# RF-learn-command-1relay-220V-capacitor.net
KiCad netlist of a schematic drawn in Altium Designer
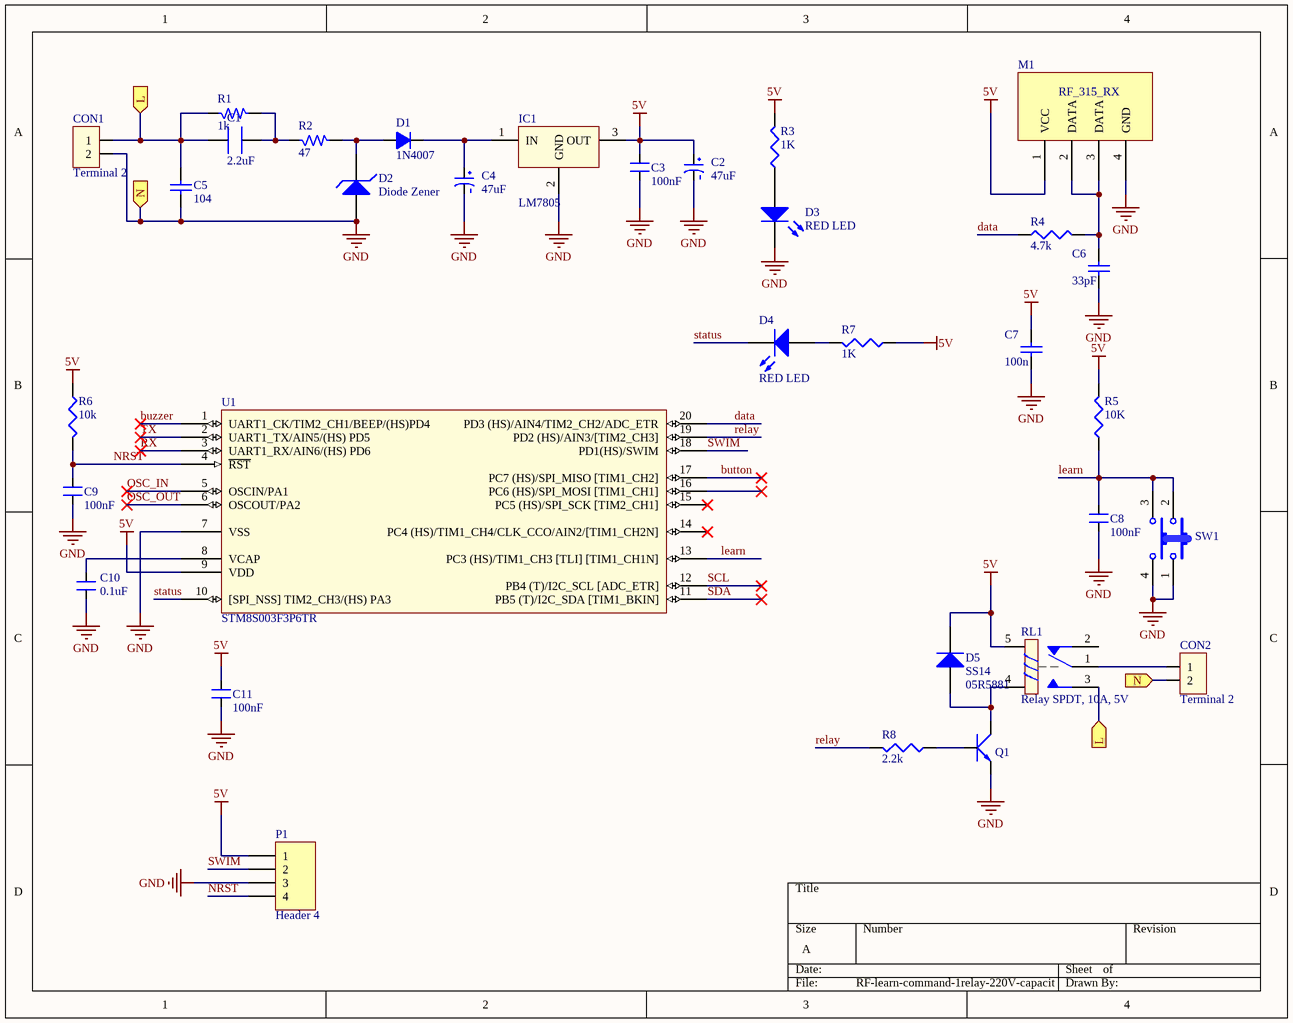
[diagram p0: RF-learn-command-1relay-220V-capacitor.SchDoc]

(export (version "E")
  (design (tool "Eeschema 10.0.6"))
  (components
    (comp (ref "C1")
      (value "2.2uF")
      (footprint "CAP 400V POLY")
      (description "DIP Electrolytic Capacitors")
      (fields (field (name "VOLTAGE") "400V") (field (name "TOLERANCE") "20%"))
      (libsource (lib "SS_Basic") (part "CAP Polyester"))
    )
    (comp (ref "C2")
      (value "47uF")
      (footprint "Capacitor 6.3")
      (description "DIP Electrolytic Capacitors")
      (fields (field (name "VOLTAGE") "35V") (field (name "TOLERANCE") "20%"))
      (libsource (lib "SS_Basic") (part "CAP DIP"))
    )
    (comp (ref "C3")
      (value "100nF")
      (footprint "ST:CM 0805")
      (description "SMD Ceramic  Capacitor")
      (fields (field (name "VOLTAGE") "50V") (field (name "TOLERANCE") "10%"))
      (libsource (lib "ST") (part "CM Ceramic"))
    )
    (comp (ref "C4")
      (value "47uF")
      (footprint "Capacitor 6.3")
      (description "DIP Electrolytic Capacitors")
      (fields (field (name "VOLTAGE") "35V") (field (name "TOLERANCE") "20%"))
      (libsource (lib "SS_Basic") (part "CAP DIP"))
    )
    (comp (ref "C5")
      (value "104")
      (footprint "C_Ceramic_KV")
      (description "Polar Capacitor")
      (fields (field (name "Comment") "Cap1") (field (name "PUBLISHER") "Altium Limited"))
      (libsource (lib "SS_Basic") (part "Cap1"))
    )
    (comp (ref "C6")
      (value "33pF")
      (footprint "ST:CM 0805")
      (description "Capacitor 100n 16V 0603")
      (fields (field (name "PUBLISHER") "Altium Limited"))
      (libsource (lib "Capacitor") (part "Cap Semi"))
    )
    (comp (ref "C7")
      (value "100n")
      (footprint "ST:CM 0805")
      (description "Capacitor 100n 16V 0603")
      (fields (field (name "PUBLISHER") "Altium Limited"))
      (libsource (lib "Capacitor") (part "Cap Semi"))
    )
    (comp (ref "C8")
      (value "100nF")
      (footprint "ST:CM 0805")
      (description "SMD Ceramic  Capacitor")
      (fields (field (name "VOLTAGE") "50V") (field (name "TOLERANCE") "10%"))
      (libsource (lib "ST") (part "CM Ceramic"))
    )
    (comp (ref "C9")
      (value "100nF")
      (footprint "ST:CM 0805")
      (description "SMD Ceramic  Capacitor")
      (fields (field (name "VOLTAGE") "50V") (field (name "TOLERANCE") "10%"))
      (libsource (lib "ST") (part "CM Ceramic"))
    )
    (comp (ref "C10")
      (value "0.1uF")
      (footprint "ST:CM 0805")
      (description "SMD Ceramic  Capacitor")
      (fields (field (name "VOLTAGE") "50V") (field (name "TOLERANCE") "10%"))
      (libsource (lib "ST") (part "CM Ceramic"))
    )
    (comp (ref "C11")
      (value "100nF")
      (footprint "ST:CM 0805")
      (description "SMD Ceramic  Capacitor")
      (fields (field (name "VOLTAGE") "50V") (field (name "TOLERANCE") "10%"))
      (libsource (lib "ST") (part "CM Ceramic"))
    )
    (comp (ref "CON1")
      (value "Terminal 2")
      (footprint "RF-learn-command-1relay-220V-capacitor:Terminal 2 5.08")
      (libsource (lib "SS_Con") (part "Terminal 2"))
    )
    (comp (ref "CON2")
      (value "Terminal 2")
      (footprint "RF-learn-command-1relay-220V-capacitor:Terminal 2 5.08")
      (libsource (lib "") (part "Terminal 2_1"))
    )
    (comp (ref "D1")
      (value "1N4007")
      (footprint "DO-214AC")
      (description "1N4007 Rectifier Diodes")
      (fields (field (name "MANUFACTURER") "SYC"))
      (libsource (lib "SS_Basic") (part "Diodes Rectifier"))
    )
    (comp (ref "D2")
      (value "Diode Zener")
      (footprint "SOD-123")
      (description "Zener Voltage Regulators")
      (fields (field (name "MANUFACTURER") "ON Semiconductor"))
      (libsource (lib "SS_Basic") (part "Diode Zener"))
    )
    (comp (ref "D3")
      (value "RED LED")
      (footprint "LED0805-R")
      (description "LED SUPR RED CLR 0805 RT ANG SMD")
      (fields
        (field (name "DIGI-KEY PART NUMBER") "160-1469-2-ND")
        (field (name "MANUFACTURER") "Lite-On Inc")
        (field (name "PUBLISHER") "Altium Limited")
      )
      (libsource (lib "Miscellaneous Devices") (part "LED2"))
    )
    (comp (ref "D4")
      (value "RED LED")
      (footprint "LED:LED3mm-Y")
      (description "LED SUPR RED CLR 0805 RT ANG SMD")
      (fields
        (field (name "DIGI-KEY PART NUMBER") "160-1469-2-ND")
        (field (name "MANUFACTURER") "Lite-On Inc")
        (field (name "PUBLISHER") "Altium Limited")
      )
      (libsource (lib "Miscellaneous Devices") (part "LED2"))
    )
    (comp (ref "D5")
      (value "SS14")
      (footprint "DO-214AC (SMA)")
      (description "DIODE GEN PURPOSE 1000V 1A SMA")
      (fields
        (field (name "DIGI-KEY PART NUMBER") "641-1018-1-ND")
        (field (name "MANUFACTURER PART NUMBER") "CGRA4007-G")
        (field (name "SUPPLIER PART NUMBER 1") "05R5881")
        (field (name "PUBLISHER") "Altium Limited")
      )
      (libsource (lib "Miscellaneous Devices") (part "Diode"))
    )
    (comp (ref "IC1")
      (value "LM7805")
      (footprint "ST:TO-252-3-L1")
      (description "On ap +, from + 5 to + 24VDC")
      (libsource (lib "syhaunguyen") (part "LM78xx"))
    )
    (comp (ref "M1")
      (value "RF_315_RX")
      (footprint "module-lib:Module-RF-RX")
      (libsource (lib "module-lib") (part "ModuleRF-RX"))
    )
    (comp (ref "P1")
      (value "Header 4")
      (footprint "SS_Con:HDR1X4")
      (description "Header, 4-Pin")
      (fields (field (name "PUBLISHER") "Altium Limited"))
      (libsource (lib "SS_Con") (part "Header 4"))
    )
    (comp (ref "Q1")
      (value "C1815")
      (footprint "2SC1815")
      (description "NPN SMD Transistor")
      (fields (field (name "MANUFACTURER") "Toshiba"))
      (libsource (lib "ST") (part "C1815"))
    )
    (comp (ref "R1")
      (value "1k")
      (footprint "R 1/4W")
      (description "Resistor 1/4W DIP")
      (libsource (lib "SS_Basic") (part "R1/4W"))
    )
    (comp (ref "R2")
      (value "47")
      (footprint "SS_Basic:R 1WD")
      (description "Resistor 1/2W DIP")
      (fields (field (name "MANUFACTURER") "UniOhm"))
      (libsource (lib "SS_Basic") (part "R1/2W"))
    )
    (comp (ref "R3")
      (value "1K")
      (footprint "R0805")
      (description "Resistor 10k 0603")
      (fields (field (name "PUBLISHER") "Altium Limited"))
      (libsource (lib "Miscellaneous Devices") (part "Res3"))
    )
    (comp (ref "R4")
      (value "4.7k")
      (footprint "R0805")
      (description "Resistor")
      (fields
        (field (name "MANUFACTURER") "Vishay / Draloric")
        (field (name "MANUFACTURER PART NUMBER") "RCV0805301KFKEA")
        (field (name "PUBLISHER") "Altium Limited")
      )
      (libsource (lib "altium-import") (part "root_0_Res3_"))
    )
    (comp (ref "R5")
      (value "10K")
      (footprint "R0805")
      (description "Resistor 10k 0603")
      (fields (field (name "PUBLISHER") "Altium Limited"))
      (libsource (lib "Miscellaneous Devices") (part "Res3"))
    )
    (comp (ref "R6")
      (value "10k")
      (footprint "R0805")
      (description "Resistor")
      (fields
        (field (name "MANUFACTURER") "Vishay / Draloric")
        (field (name "MANUFACTURER PART NUMBER") "RCV0805301KFKEA")
        (field (name "PUBLISHER") "Altium Limited")
      )
      (libsource (lib "altium-import") (part "root_3_Res3_"))
    )
    (comp (ref "R7")
      (value "1K")
      (footprint "R0805")
      (description "Resistor 10k 0603")
      (fields (field (name "PUBLISHER") "Altium Limited"))
      (libsource (lib "Miscellaneous Devices") (part "Res3"))
    )
    (comp (ref "R8")
      (value "2.2k")
      (footprint "R0805")
      (description "Resistor")
      (fields
        (field (name "MANUFACTURER") "Vishay / Draloric")
        (field (name "MANUFACTURER PART NUMBER") "RCV0805301KFKEA")
        (field (name "PUBLISHER") "Altium Limited")
      )
      (libsource (lib "altium-import") (part "root_2_Res3_"))
    )
    (comp (ref "RL1")
      (value "Relay SPDT, 10A, 5V")
      (footprint "RL_SPDT_10A")
      (description "Relay SPDT,10A - 12VDC 5 Pin")
      (libsource (lib "nhantt-relay-lib") (part "Relay 1"))
    )
    (comp (ref "SW1")
      (value "SW-4P-S")
      (footprint "SW4")
      (description "Switch Small 4 Pin")
      (fields (field (name "PUBLISHER") "Altium Limited"))
      (libsource (lib "Schematic") (part "SW-4PIN-SMALL"))
    )
    (comp (ref "U1")
      (value "STM8S003F3P6TR")
      (footprint "SSOP-20")
      (description "MCU")
      (fields (field (name "MANUFACTURER") "STMicroelectronics"))
      (libsource (lib "mcu-lib") (part "STM8S003F3"))
    )
  )
  (nets
    (net (code "1") (name "/L") (class "Default")
      (node (ref "C1") (pin "1") (pinfunction "1_1") (pintype "passive"))
      (node (ref "C5") (pin "2") (pinfunction "2_2") (pintype "passive"))
      (node (ref "CON1") (pin "1") (pinfunction "1_1") (pintype "passive"))
      (node (ref "R1") (pin "1") (pinfunction "1_1") (pintype "passive"))
      (node (ref "RL1") (pin "3") (pinfunction "3_3") (pintype "passive"))
    )
    (net (code "2") (name "/NRST") (class "Default")
      (node (ref "C9") (pin "2") (pinfunction "2_2") (pintype "passive"))
      (node (ref "P1") (pin "4") (pinfunction "4_4") (pintype "passive"))
      (node (ref "R6") (pin "2") (pinfunction "2_2") (pintype "passive"))
      (node (ref "U1") (pin "4") (pinfunction "~{RST}_4") (pintype "input"))
    )
    (net (code "3") (name "/OSC_IN") (class "Default")
      (node (ref "U1") (pin "5") (pinfunction "OSCIN/PA1_5") (pintype "bidirectional+no_connect"))
    )
    (net (code "4") (name "/OSC_OUT") (class "Default")
      (node (ref "U1") (pin "6") (pinfunction "OSCOUT/PA2_6") (pintype "bidirectional+no_connect"))
    )
    (net (code "5") (name "/RX") (class "Default")
      (node (ref "U1") (pin "3") (pinfunction "UART1_RX/AIN6/(HS)_PD6_3") (pintype "bidirectional+no_connect"))
    )
    (net (code "6") (name "/SCL") (class "Default")
      (node (ref "U1") (pin "12") (pinfunction "PB4_(T)/I2C_SCL_[ADC_ETR]_12") (pintype "bidirectional+no_connect"))
    )
    (net (code "7") (name "/SDA") (class "Default")
      (node (ref "U1") (pin "11") (pinfunction "PB5_(T)/I2C_SDA_[TIM1_BKIN]_11") (pintype "bidirectional+no_connect"))
    )
    (net (code "8") (name "/SWIM") (class "Default")
      (node (ref "P1") (pin "2") (pinfunction "2_2") (pintype "passive"))
      (node (ref "U1") (pin "18") (pinfunction "PD1(HS)/SWIM_18") (pintype "bidirectional"))
    )
    (net (code "9") (name "/TX") (class "Default")
      (node (ref "U1") (pin "2") (pinfunction "UART1_TX/AIN5/(HS)_PD5_2") (pintype "bidirectional+no_connect"))
    )
    (net (code "10") (name "/button") (class "Default")
      (node (ref "U1") (pin "17") (pinfunction "PC7_(HS)/SPI_MISO_[TIM1_CH2]_17") (pintype "bidirectional+no_connect"))
    )
    (net (code "11") (name "/buzzer") (class "Default")
      (node (ref "U1") (pin "1") (pinfunction "UART1_CK/TIM2_CH1/BEEP/(HS)PD4_1") (pintype "bidirectional+no_connect"))
    )
    (net (code "12") (name "/data") (class "Default")
      (node (ref "R4") (pin "1") (pinfunction "1_1") (pintype "passive"))
      (node (ref "U1") (pin "20") (pinfunction "PD3_(HS)/AIN4/TIM2_CH2/ADC_ETR_20") (pintype "bidirectional"))
    )
    (net (code "13") (name "/learn") (class "Default")
      (node (ref "C8") (pin "2") (pinfunction "2_2") (pintype "passive"))
      (node (ref "R5") (pin "1") (pinfunction "1_1") (pintype "passive"))
      (node (ref "SW1") (pin "2") (pinfunction "2_2") (pintype "passive"))
      (node (ref "SW1") (pin "3") (pinfunction "3_3") (pintype "passive"))
      (node (ref "U1") (pin "13") (pinfunction "PC3_(HS)/TIM1_CH3_[TLI]_[TIM1_CH1N]_13") (pintype "bidirectional"))
    )
    (net (code "14") (name "/relay") (class "Default")
      (node (ref "R8") (pin "2") (pinfunction "2_2") (pintype "passive"))
      (node (ref "U1") (pin "19") (pinfunction "PD2_(HS)/AIN3/[TIM2_CH3]_19") (pintype "bidirectional"))
    )
    (net (code "15") (name "/status") (class "Default")
      (node (ref "D4") (pin "2") (pinfunction "K_2") (pintype "passive"))
      (node (ref "U1") (pin "10") (pinfunction "[SPI_NSS]_TIM2_CH3/(HS)_PA3_10") (pintype "bidirectional"))
    )
    (net (code "16") (name "5V") (class "Default")
      (node (ref "C11") (pin "2") (pinfunction "2_2") (pintype "passive"))
      (node (ref "C2") (pin "1") (pinfunction "1_1") (pintype "passive"))
      (node (ref "C3") (pin "2") (pinfunction "2_2") (pintype "passive"))
      (node (ref "C7") (pin "1") (pinfunction "1_1") (pintype "passive"))
      (node (ref "D5") (pin "2") (pinfunction "K_2") (pintype "passive"))
      (node (ref "IC1") (pin "3") (pinfunction "OUT_3") (pintype "passive"))
      (node (ref "M1") (pin "1") (pinfunction "VCC_1") (pintype "passive"))
      (node (ref "P1") (pin "1") (pinfunction "1_1") (pintype "passive"))
      (node (ref "R3") (pin "2") (pinfunction "2_2") (pintype "passive"))
      (node (ref "R5") (pin "2") (pinfunction "2_2") (pintype "passive"))
      (node (ref "R6") (pin "1") (pinfunction "1_1") (pintype "passive"))
      (node (ref "R7") (pin "1") (pinfunction "1_1") (pintype "passive"))
      (node (ref "RL1") (pin "5") (pinfunction "5_5") (pintype "passive"))
      (node (ref "U1") (pin "9") (pinfunction "VDD_9") (pintype "power_in"))
    )
    (net (code "17") (name "GND") (class "Default")
      (node (ref "C10") (pin "1") (pinfunction "1_1") (pintype "passive"))
      (node (ref "C11") (pin "1") (pinfunction "1_1") (pintype "passive"))
      (node (ref "C2") (pin "2") (pinfunction "2_2") (pintype "passive"))
      (node (ref "C3") (pin "1") (pinfunction "1_1") (pintype "passive"))
      (node (ref "C4") (pin "2") (pinfunction "2_2") (pintype "passive"))
      (node (ref "C5") (pin "1") (pinfunction "1_1") (pintype "passive"))
      (node (ref "C6") (pin "2") (pinfunction "2_2") (pintype "passive"))
      (node (ref "C7") (pin "2") (pinfunction "2_2") (pintype "passive"))
      (node (ref "C8") (pin "1") (pinfunction "1_1") (pintype "passive"))
      (node (ref "C9") (pin "1") (pinfunction "1_1") (pintype "passive"))
      (node (ref "CON1") (pin "2") (pinfunction "2_2") (pintype "passive"))
      (node (ref "CON2") (pin "2") (pinfunction "2_2") (pintype "passive"))
      (node (ref "D2") (pin "2") (pinfunction "A_2") (pintype "passive"))
      (node (ref "D3") (pin "2") (pinfunction "K_2") (pintype "passive"))
      (node (ref "IC1") (pin "2") (pinfunction "GND_2") (pintype "passive"))
      (node (ref "M1") (pin "4") (pinfunction "GND_4") (pintype "passive"))
      (node (ref "P1") (pin "3") (pinfunction "3_3") (pintype "passive"))
      (node (ref "Q1") (pin "2") (pinfunction "E_2") (pintype "passive"))
      (node (ref "SW1") (pin "1") (pinfunction "1_1") (pintype "passive"))
      (node (ref "SW1") (pin "4") (pinfunction "4_4") (pintype "passive"))
      (node (ref "U1") (pin "7") (pinfunction "VSS_7") (pintype "power_in"))
    )
    (net (code "18") (name "Net-(C1-Pad2)") (class "Default")
      (node (ref "C1") (pin "2") (pinfunction "2_2") (pintype "passive"))
      (node (ref "R1") (pin "2") (pinfunction "2_2") (pintype "passive"))
      (node (ref "R2") (pin "1") (pinfunction "1_1") (pintype "passive"))
    )
    (net (code "19") (name "Net-(C6-Pad1)") (class "Default")
      (node (ref "C6") (pin "1") (pinfunction "1_1") (pintype "passive"))
      (node (ref "M1") (pin "2") (pinfunction "DATA_2") (pintype "passive"))
      (node (ref "M1") (pin "3") (pinfunction "DATA_3") (pintype "passive"))
      (node (ref "R4") (pin "2") (pinfunction "2_2") (pintype "passive"))
    )
    (net (code "20") (name "Net-(CON2-Pad1)") (class "Default")
      (node (ref "CON2") (pin "1") (pinfunction "1_1") (pintype "passive"))
      (node (ref "RL1") (pin "1") (pinfunction "1_1") (pintype "passive"))
    )
    (net (code "21") (name "Net-(D1-A)") (class "Default")
      (node (ref "D1") (pin "2") (pinfunction "A_2") (pintype "passive"))
      (node (ref "D2") (pin "1") (pinfunction "K_1") (pintype "passive"))
      (node (ref "R2") (pin "2") (pinfunction "2_2") (pintype "passive"))
    )
    (net (code "22") (name "Net-(D1-K)") (class "Default")
      (node (ref "C4") (pin "1") (pinfunction "1_1") (pintype "passive"))
      (node (ref "D1") (pin "1") (pinfunction "K_1") (pintype "passive"))
      (node (ref "IC1") (pin "1") (pinfunction "IN_1") (pintype "passive"))
    )
    (net (code "23") (name "Net-(D3-A)") (class "Default")
      (node (ref "D3") (pin "1") (pinfunction "A_1") (pintype "passive"))
      (node (ref "R3") (pin "1") (pinfunction "1_1") (pintype "passive"))
    )
    (net (code "24") (name "Net-(D4-A)") (class "Default")
      (node (ref "D4") (pin "1") (pinfunction "A_1") (pintype "passive"))
      (node (ref "R7") (pin "2") (pinfunction "2_2") (pintype "passive"))
    )
    (net (code "25") (name "Net-(D5-A)") (class "Default")
      (node (ref "D5") (pin "1") (pinfunction "A_1") (pintype "passive"))
      (node (ref "Q1") (pin "3") (pinfunction "C_3") (pintype "passive"))
      (node (ref "RL1") (pin "4") (pinfunction "4_4") (pintype "passive"))
    )
    (net (code "26") (name "Net-(Q1-B)") (class "Default")
      (node (ref "Q1") (pin "1") (pinfunction "B_1") (pintype "passive"))
      (node (ref "R8") (pin "1") (pinfunction "1_1") (pintype "passive"))
    )
    (net (code "27") (name "Net-(U1-VCAP)") (class "Default")
      (node (ref "C10") (pin "2") (pinfunction "2_2") (pintype "passive"))
      (node (ref "U1") (pin "8") (pinfunction "VCAP_8") (pintype "power_in"))
    )
    (net (code "28") (name "unconnected-(RL1-Pad2)") (class "Default")
      (node (ref "RL1") (pin "2") (pinfunction "2_2") (pintype "passive"))
    )
    (net (code "29") (name "unconnected-(U1-PC4_(HS){slash}TIM1_CH4{slash}CLK_CCO{slash}AIN2{slash}[TIM1_CH2N]-Pad14)") (class "Default")
      (node (ref "U1") (pin "14") (pinfunction "PC4_(HS)/TIM1_CH4/CLK_CCO/AIN2/[TIM1_CH2N]_14") (pintype "bidirectional+no_connect"))
    )
    (net (code "30") (name "unconnected-(U1-PC5_(HS){slash}SPI_SCK_[TIM2_CH1]-Pad15)") (class "Default")
      (node (ref "U1") (pin "15") (pinfunction "PC5_(HS)/SPI_SCK_[TIM2_CH1]_15") (pintype "bidirectional+no_connect"))
    )
    (net (code "31") (name "unconnected-(U1-PC6_(HS){slash}SPI_MOSI_[TIM1_CH1]-Pad16)") (class "Default")
      (node (ref "U1") (pin "16") (pinfunction "PC6_(HS)/SPI_MOSI_[TIM1_CH1]_16") (pintype "bidirectional+no_connect"))
    )
  )
)
